# board.net
KiCad netlist of a schematic drawn in EAGLE
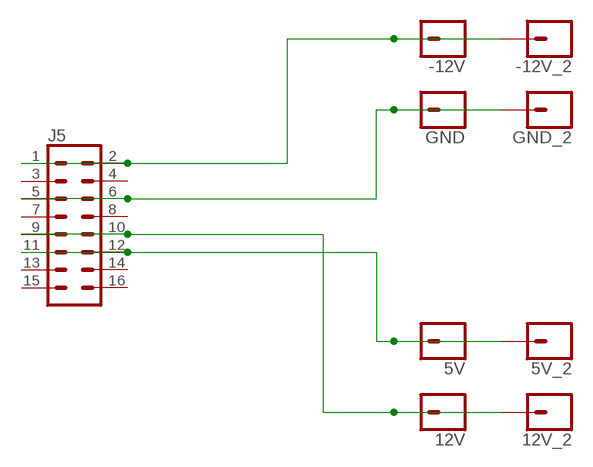
[diagram p0: schematic, sheet 1]

(export (version "E")
  (design (tool "Eeschema 10.0.6"))
  (components
    (comp (ref "-12V")
      (value "CONN_01")
      (footprint "eagle-import:1X01")
      (libsource (lib "eagle-import") (part "CONN_01"))
    )
    (comp (ref "-12V_2")
      (value "CONN_01")
      (footprint "eagle-import:1X01")
      (libsource (lib "eagle-import") (part "CONN_01"))
    )
    (comp (ref "5V")
      (value "CONN_01")
      (footprint "eagle-import:1X01")
      (libsource (lib "eagle-import") (part "CONN_01"))
    )
    (comp (ref "5V_2")
      (value "CONN_01")
      (footprint "eagle-import:1X01")
      (libsource (lib "eagle-import") (part "CONN_01"))
    )
    (comp (ref "12V")
      (value "CONN_01")
      (footprint "eagle-import:1X01")
      (libsource (lib "eagle-import") (part "CONN_01"))
    )
    (comp (ref "12V_2")
      (value "CONN_01")
      (footprint "eagle-import:1X01")
      (libsource (lib "eagle-import") (part "CONN_01"))
    )
    (comp (ref "GND")
      (value "CONN_01")
      (footprint "eagle-import:1X01")
      (libsource (lib "eagle-import") (part "CONN_01"))
    )
    (comp (ref "GND_2")
      (value "CONN_01")
      (footprint "eagle-import:1X01")
      (libsource (lib "eagle-import") (part "CONN_01"))
    )
    (comp (ref "J5")
      (value "CONN_08X2")
      (footprint "eagle-import:2X8")
      (libsource (lib "eagle-import") (part "CONN_08X2"))
    )
  )
  (nets
    (net (code "1") (name "Net-(-12V-Pad1)") (class "Default")
      (node (ref "-12V") (pin "1") (pinfunction "1_1") (pintype "passive"))
      (node (ref "-12V_2") (pin "1") (pinfunction "1_1") (pintype "passive"))
      (node (ref "J5") (pin "1") (pinfunction "1_1") (pintype "passive"))
      (node (ref "J5") (pin "2") (pinfunction "2_2") (pintype "passive"))
    )
    (net (code "2") (name "Net-(5V-Pad1)") (class "Default")
      (node (ref "5V") (pin "1") (pinfunction "1_1") (pintype "passive"))
      (node (ref "5V_2") (pin "1") (pinfunction "1_1") (pintype "passive"))
      (node (ref "J5") (pin "11") (pinfunction "11_11") (pintype "passive"))
      (node (ref "J5") (pin "12") (pinfunction "12_12") (pintype "passive"))
    )
    (net (code "3") (name "Net-(12V-Pad1)") (class "Default")
      (node (ref "12V") (pin "1") (pinfunction "1_1") (pintype "passive"))
      (node (ref "12V_2") (pin "1") (pinfunction "1_1") (pintype "passive"))
      (node (ref "J5") (pin "10") (pinfunction "10_10") (pintype "passive"))
      (node (ref "J5") (pin "9") (pinfunction "9_9") (pintype "passive"))
    )
    (net (code "4") (name "Net-(GND-Pad1)") (class "Default")
      (node (ref "GND") (pin "1") (pinfunction "1_1") (pintype "passive"))
      (node (ref "GND_2") (pin "1") (pinfunction "1_1") (pintype "passive"))
      (node (ref "J5") (pin "5") (pinfunction "5_5") (pintype "passive"))
      (node (ref "J5") (pin "6") (pinfunction "6_6") (pintype "passive"))
    )
    (net (code "5") (name "unconnected-(J5-Pad3)") (class "Default")
      (node (ref "J5") (pin "3") (pinfunction "3_3") (pintype "passive"))
    )
    (net (code "6") (name "unconnected-(J5-Pad4)") (class "Default")
      (node (ref "J5") (pin "4") (pinfunction "4_4") (pintype "passive"))
    )
    (net (code "7") (name "unconnected-(J5-Pad7)") (class "Default")
      (node (ref "J5") (pin "7") (pinfunction "7_7") (pintype "passive"))
    )
    (net (code "8") (name "unconnected-(J5-Pad8)") (class "Default")
      (node (ref "J5") (pin "8") (pinfunction "8_8") (pintype "passive"))
    )
    (net (code "9") (name "unconnected-(J5-Pad13)") (class "Default")
      (node (ref "J5") (pin "13") (pinfunction "13_13") (pintype "passive"))
    )
    (net (code "10") (name "unconnected-(J5-Pad14)") (class "Default")
      (node (ref "J5") (pin "14") (pinfunction "14_14") (pintype "passive"))
    )
    (net (code "11") (name "unconnected-(J5-Pad15)") (class "Default")
      (node (ref "J5") (pin "15") (pinfunction "15_15") (pintype "passive"))
    )
    (net (code "12") (name "unconnected-(J5-Pad16)") (class "Default")
      (node (ref "J5") (pin "16") (pinfunction "16_16") (pintype "passive"))
    )
  )
)
